# zhuzhuan1.net
KiCad netlist of a schematic drawn in Altium Designer
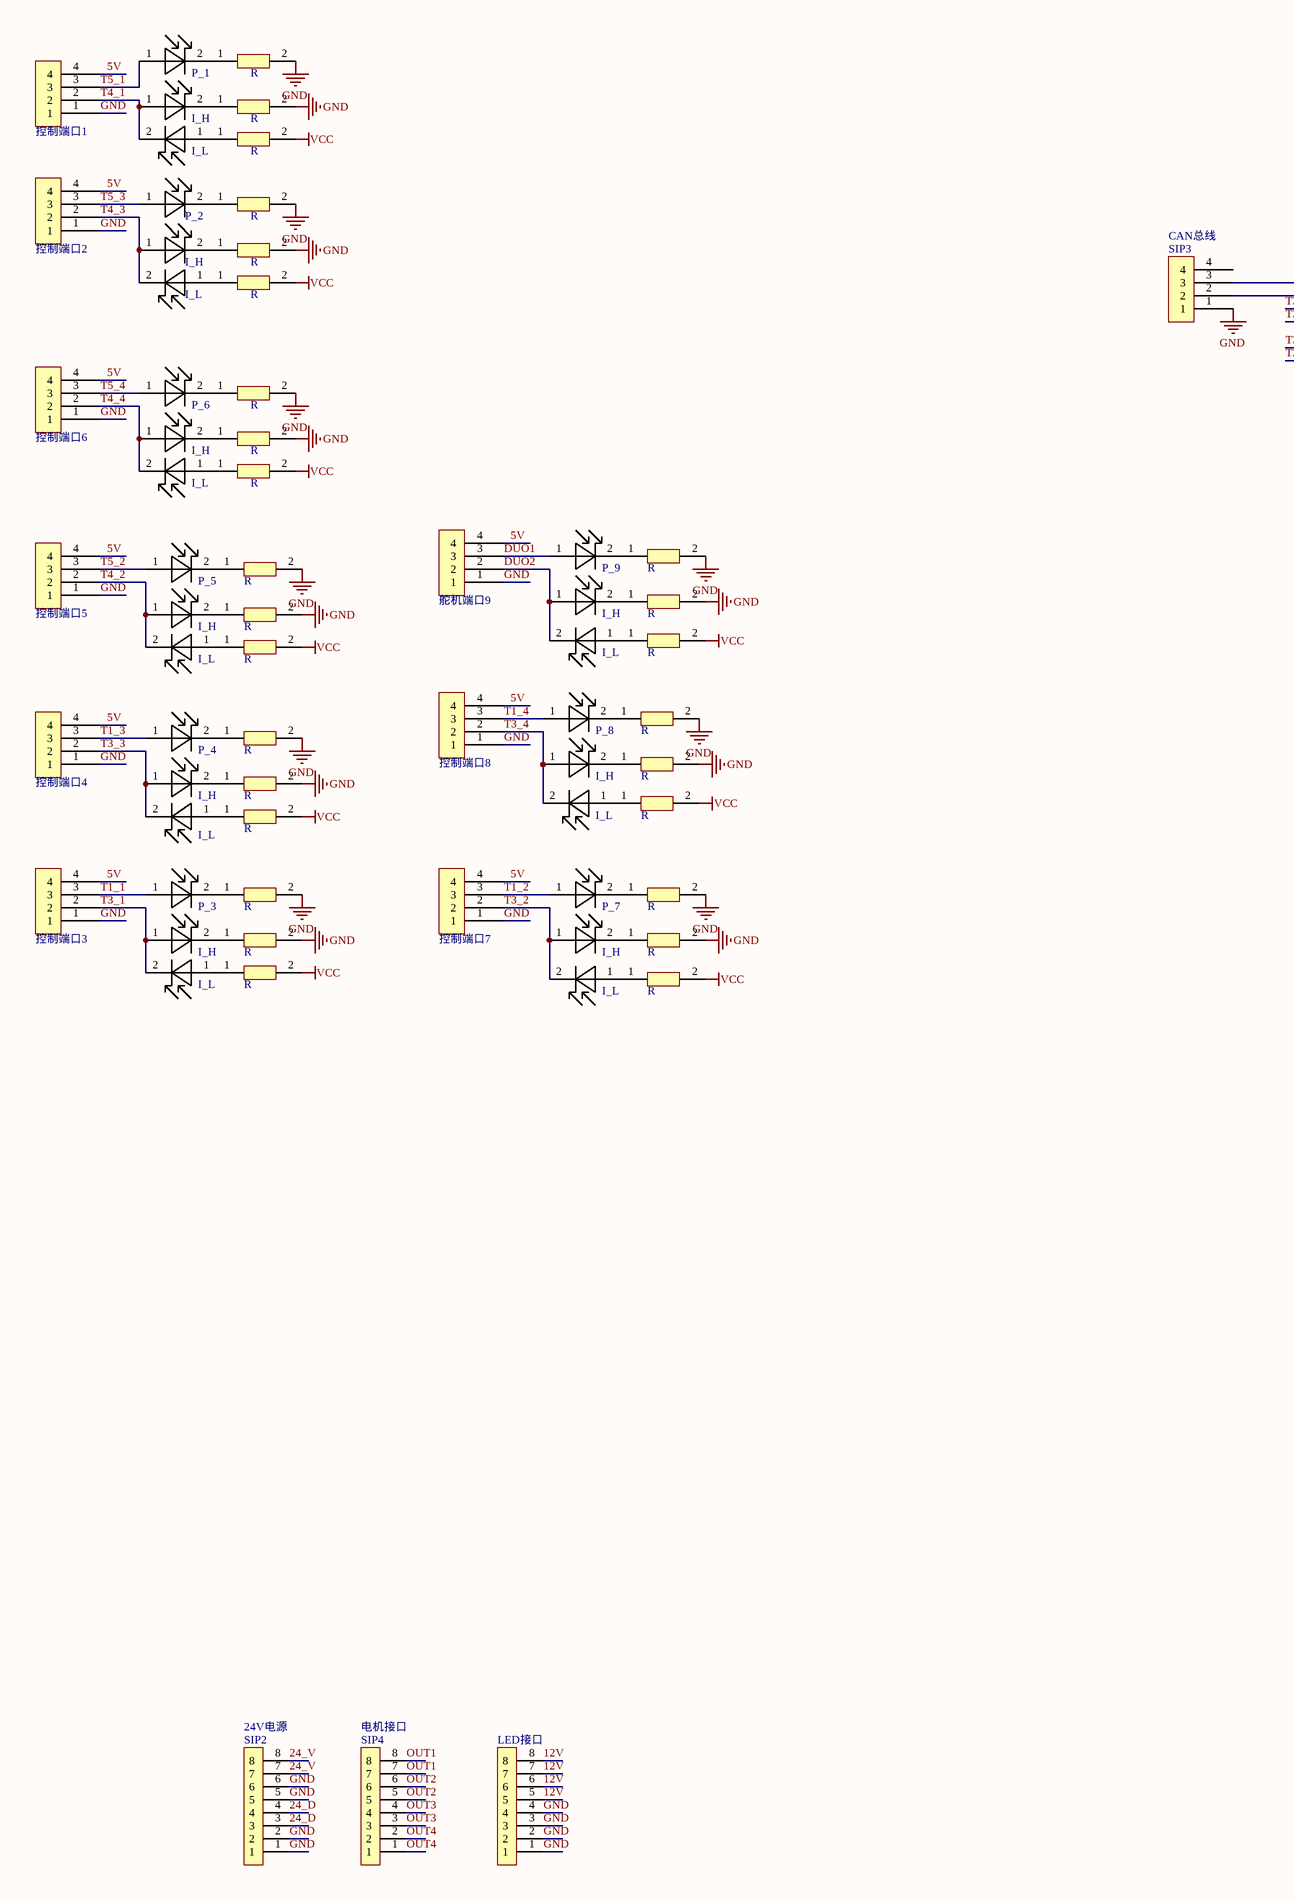
[diagram p0: zhuzhuan1.SchDoc, left]
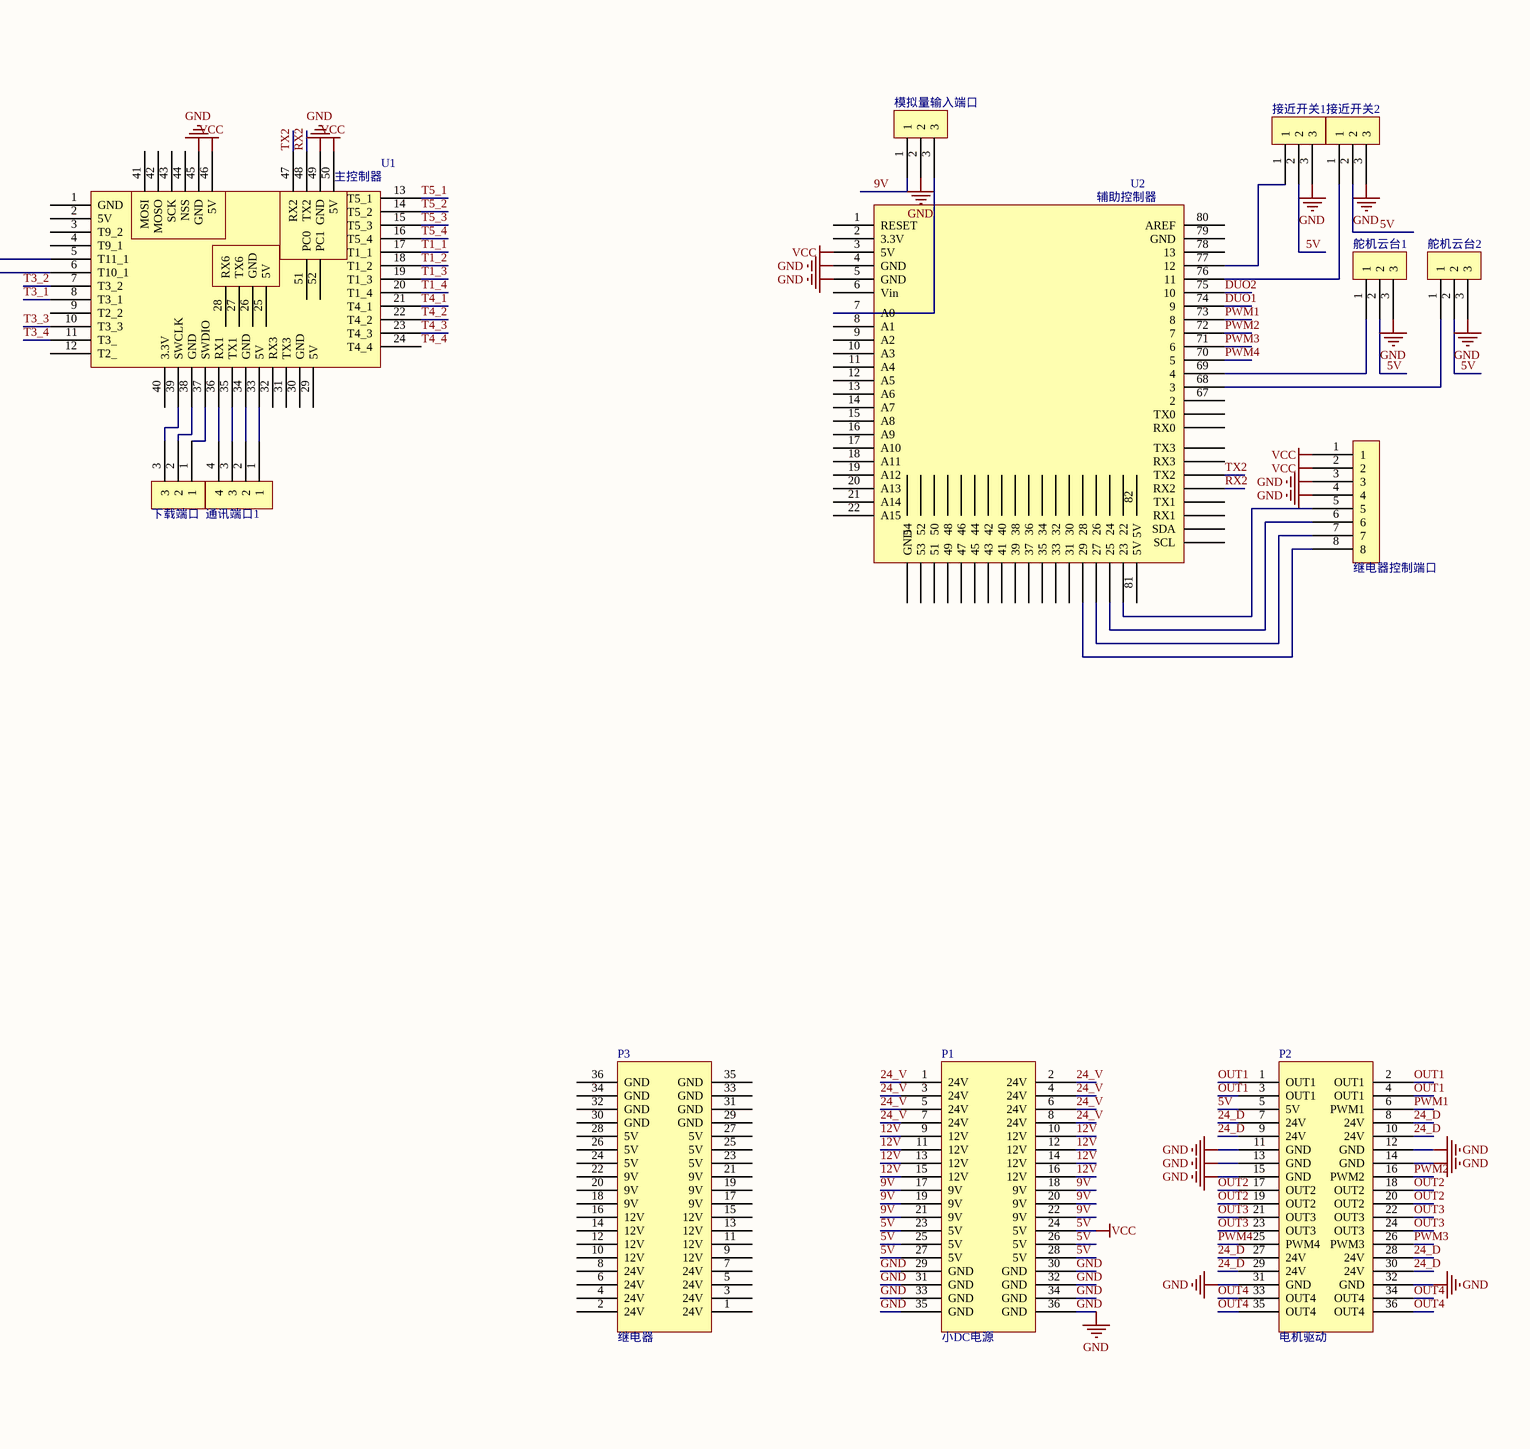
[diagram p1: zhuzhuan1.SchDoc, right]

(export (version "E")
  (design (tool "Eeschema 10.0.6"))
  (components
    (comp (ref "L1") (value "P_1") (footprint "LED-T") (libsource (lib "qudong") (part "LED")))
    (comp (ref "L2") (value "I_H") (footprint "LED-T") (libsource (lib "qudong") (part "LED")))
    (comp (ref "L3") (value "I_L") (footprint "LED-T") (libsource (lib "qudong") (part "LED")))
    (comp (ref "L4") (value "P_2") (footprint "LED-T") (libsource (lib "qudong") (part "LED")))
    (comp (ref "L5") (value "I_H") (footprint "LED-T") (libsource (lib "qudong") (part "LED")))
    (comp (ref "L6") (value "I_L") (footprint "LED-T") (libsource (lib "qudong") (part "LED")))
    (comp (ref "L7") (value "P_3") (footprint "LED-T") (libsource (lib "qudong") (part "LED")))
    (comp (ref "L8") (value "I_H") (footprint "LED-T") (libsource (lib "qudong") (part "LED")))
    (comp (ref "L9") (value "I_L") (footprint "LED-T") (libsource (lib "qudong") (part "LED")))
    (comp (ref "L10") (value "P_4") (footprint "LED-T") (libsource (lib "qudong") (part "LED")))
    (comp (ref "L11") (value "I_H") (footprint "LED-T") (libsource (lib "qudong") (part "LED")))
    (comp (ref "L12") (value "I_L") (footprint "LED-T") (libsource (lib "qudong") (part "LED")))
    (comp (ref "L13") (value "P_5") (footprint "LED-T") (libsource (lib "qudong") (part "LED")))
    (comp (ref "L14") (value "I_H") (footprint "LED-T") (libsource (lib "qudong") (part "LED")))
    (comp (ref "L15") (value "I_L") (footprint "LED-T") (libsource (lib "qudong") (part "LED")))
    (comp (ref "L16") (value "P_6") (footprint "LED-T") (libsource (lib "qudong") (part "LED")))
    (comp (ref "L17") (value "I_H") (footprint "LED-T") (libsource (lib "qudong") (part "LED")))
    (comp (ref "L18") (value "I_L") (footprint "LED-T") (libsource (lib "qudong") (part "LED")))
    (comp (ref "L19") (value "P_7") (footprint "LED-T") (libsource (lib "qudong") (part "LED")))
    (comp (ref "L20") (value "I_H") (footprint "LED-T") (libsource (lib "qudong") (part "LED")))
    (comp (ref "L21") (value "I_L") (footprint "LED-T") (libsource (lib "qudong") (part "LED")))
    (comp (ref "L22") (value "P_8") (footprint "LED-T") (libsource (lib "qudong") (part "LED")))
    (comp (ref "L23") (value "I_H") (footprint "LED-T") (libsource (lib "qudong") (part "LED")))
    (comp (ref "L24") (value "I_L") (footprint "LED-T") (libsource (lib "qudong") (part "LED")))
    (comp (ref "L25") (value "P_9") (footprint "LED-T") (libsource (lib "qudong") (part "LED")))
    (comp (ref "L26") (value "I_H") (footprint "LED-T") (libsource (lib "qudong") (part "LED")))
    (comp (ref "L27") (value "I_L") (footprint "LED-T") (libsource (lib "qudong") (part "LED")))
    (comp (ref "P1") (value "小DC电源") (footprint "DIP36-3.96MM") (libsource (lib "") (part "POWER_18*2_1")))
    (comp (ref "P2") (value "电机驱动") (footprint "DIP36-3.96MM") (libsource (lib "qudong") (part "Header")))
    (comp (ref "P3") (value "继电器") (footprint "DIP36-3.96MM") (libsource (lib "qudong") (part "POWER_18*2")))
    (comp (ref "R1") (value "R") (footprint "RES-T") (libsource (lib "qudong") (part "RES-T")))
    (comp (ref "R2") (value "R") (footprint "RES-T") (libsource (lib "qudong") (part "RES-T")))
    (comp (ref "R3") (value "R") (footprint "RES-T") (libsource (lib "qudong") (part "RES-T")))
    (comp (ref "R4") (value "R") (footprint "RES-T") (libsource (lib "qudong") (part "RES-T")))
    (comp (ref "R5") (value "R") (footprint "RES-T") (libsource (lib "qudong") (part "RES-T")))
    (comp (ref "R6") (value "R") (footprint "RES-T") (libsource (lib "qudong") (part "RES-T")))
    (comp (ref "R7") (value "R") (footprint "RES-T") (libsource (lib "qudong") (part "RES-T")))
    (comp (ref "R8") (value "R") (footprint "RES-T") (libsource (lib "qudong") (part "RES-T")))
    (comp (ref "R9") (value "R") (footprint "RES-T") (libsource (lib "qudong") (part "RES-T")))
    (comp (ref "R10") (value "R") (footprint "RES-T") (libsource (lib "qudong") (part "RES-T")))
    (comp (ref "R11") (value "R") (footprint "RES-T") (libsource (lib "qudong") (part "RES-T")))
    (comp (ref "R12") (value "R") (footprint "RES-T") (libsource (lib "qudong") (part "RES-T")))
    (comp (ref "R13") (value "R") (footprint "RES-T") (libsource (lib "qudong") (part "RES-T")))
    (comp (ref "R14") (value "R") (footprint "RES-T") (libsource (lib "qudong") (part "RES-T")))
    (comp (ref "R15") (value "R") (footprint "RES-T") (libsource (lib "qudong") (part "RES-T")))
    (comp (ref "R16") (value "R") (footprint "RES-T") (libsource (lib "qudong") (part "RES-T")))
    (comp (ref "R17") (value "R") (footprint "RES-T") (libsource (lib "qudong") (part "RES-T")))
    (comp (ref "R18") (value "R") (footprint "RES-T") (libsource (lib "qudong") (part "RES-T")))
    (comp (ref "R19") (value "R") (footprint "RES-T") (libsource (lib "qudong") (part "RES-T")))
    (comp (ref "R20") (value "R") (footprint "RES-T") (libsource (lib "qudong") (part "RES-T")))
    (comp (ref "R21") (value "R") (footprint "RES-T") (libsource (lib "qudong") (part "RES-T")))
    (comp (ref "R22") (value "R") (footprint "RES-T") (libsource (lib "qudong") (part "RES-T")))
    (comp (ref "R23") (value "R") (footprint "RES-T") (libsource (lib "qudong") (part "RES-T")))
    (comp (ref "R24") (value "R") (footprint "RES-T") (libsource (lib "qudong") (part "RES-T")))
    (comp (ref "R25") (value "R") (footprint "RES-T") (libsource (lib "qudong") (part "RES-T")))
    (comp (ref "R26") (value "R") (footprint "RES-T") (libsource (lib "qudong") (part "RES-T")))
    (comp (ref "R27") (value "R") (footprint "RES-T") (libsource (lib "qudong") (part "RES-T")))
    (comp (ref "SIP2") (value "24V电源") (footprint "SIP8*3MM") (libsource (lib "qudong") (part "SIP8*3MM")))
    (comp (ref "SIP3") (value "CAN总线") (footprint "SIP4") (libsource (lib "qudong") (part "SIP4")))
    (comp (ref "SIP4") (value "电机接口") (footprint "SIP8*3MM") (libsource (lib "qudong") (part "SIP8*3MM")))
    (comp (ref "SIP5") (value "下载端口") (footprint "SIP3") (libsource (lib "") (part "SIP3_1")))
    (comp (ref "SIP7") (value "控制端口1") (footprint "SIP4") (libsource (lib "qudong") (part "SIP4")))
    (comp (ref "SIP8") (value "控制端口2") (footprint "SIP4") (libsource (lib "qudong") (part "SIP4")))
    (comp (ref "SIP9") (value "控制端口3") (footprint "SIP4") (libsource (lib "qudong") (part "SIP4")))
    (comp (ref "SIP10") (value "控制端口4") (footprint "SIP4") (libsource (lib "qudong") (part "SIP4")))
    (comp (ref "SIP11") (value "控制端口5") (footprint "SIP4") (libsource (lib "qudong") (part "SIP4")))
    (comp (ref "SIP12") (value "控制端口6") (footprint "SIP4") (libsource (lib "qudong") (part "SIP4")))
    (comp (ref "SIP13") (value "控制端口7") (footprint "SIP4") (libsource (lib "qudong") (part "SIP4")))
    (comp (ref "SIP14") (value "控制端口8") (footprint "SIP4") (libsource (lib "qudong") (part "SIP4")))
    (comp (ref "SIP15") (value "舵机云台1") (footprint "SIP3-3MM") (libsource (lib "qudong") (part "SIP3")))
    (comp (ref "SIP16") (value "舵机云台2") (footprint "SIP3-3MM") (libsource (lib "qudong") (part "SIP3")))
    (comp (ref "SIP17") (value "模拟量输入端口") (footprint "SIP3-3MM") (libsource (lib "qudong") (part "SIP3")))
    (comp (ref "SIP18") (value "舵机端口9") (footprint "SIP4") (libsource (lib "qudong") (part "SIP4")))
    (comp (ref "SIP19") (value "LED接口") (footprint "SIP8*3MM") (libsource (lib "qudong") (part "SIP8*3MM")))
    (comp (ref "SIP20") (value "接近开关1") (footprint "SIP3-3MM") (libsource (lib "qudong") (part "SIP3")))
    (comp (ref "SIP21") (value "接近开关2") (footprint "SIP3-3MM") (libsource (lib "qudong") (part "SIP3")))
    (comp (ref "SIP22") (value "继电器控制端口") (footprint "SIP8") (libsource (lib "qudong") (part "SIP8")))
    (comp (ref "U1")
      (value "主控制器")
      (footprint "-----STM32F407-----")
      (libsource (lib "qudong") (part "------STM32F407------"))
    )
    (comp (ref "U2")
      (value "辅助控制器")
      (footprint "ARDUINO 2560")
      (libsource (lib "qudong") (part "ARDUINO 2560"))
    )
    (comp (ref "通讯端口1") (value "SIP4") (footprint "SIP4") (libsource (lib "") (part "SIP4_1")))
  )
  (nets
    (net (code "1") (name "/9V") (class "Default")
      (node (ref "P1") (pin "17") (pinfunction "9V_17") (pintype "passive"))
      (node (ref "P1") (pin "18") (pinfunction "9V_18") (pintype "passive"))
      (node (ref "P1") (pin "19") (pinfunction "9V_19") (pintype "passive"))
      (node (ref "P1") (pin "20") (pinfunction "9V_20") (pintype "passive"))
      (node (ref "P1") (pin "21") (pinfunction "9V_21") (pintype "passive"))
      (node (ref "P1") (pin "22") (pinfunction "9V_22") (pintype "passive"))
      (node (ref "SIP17") (pin "1") (pinfunction "1_1") (pintype "passive"))
    )
    (net (code "2") (name "/12V") (class "Default")
      (node (ref "P1") (pin "10") (pinfunction "12V_10") (pintype "passive"))
      (node (ref "P1") (pin "11") (pinfunction "12V_11") (pintype "passive"))
      (node (ref "P1") (pin "12") (pinfunction "12V_12") (pintype "passive"))
      (node (ref "P1") (pin "13") (pinfunction "12V_13") (pintype "passive"))
      (node (ref "P1") (pin "14") (pinfunction "12V_14") (pintype "passive"))
      (node (ref "P1") (pin "15") (pinfunction "12V_15") (pintype "passive"))
      (node (ref "P1") (pin "16") (pinfunction "12V_16") (pintype "passive"))
      (node (ref "P1") (pin "9") (pinfunction "12V_9") (pintype "passive"))
      (node (ref "SIP19") (pin "5") (pinfunction "5_5") (pintype "passive"))
      (node (ref "SIP19") (pin "6") (pinfunction "6_6") (pintype "passive"))
      (node (ref "SIP19") (pin "7") (pinfunction "7_7") (pintype "passive"))
      (node (ref "SIP19") (pin "8") (pinfunction "8_8") (pintype "passive"))
    )
    (net (code "3") (name "/24_D") (class "Default")
      (node (ref "P2") (pin "10") (pinfunction "24V_10") (pintype "passive"))
      (node (ref "P2") (pin "27") (pinfunction "24V_27") (pintype "passive"))
      (node (ref "P2") (pin "28") (pinfunction "24V_28") (pintype "passive"))
      (node (ref "P2") (pin "29") (pinfunction "24V_29") (pintype "passive"))
      (node (ref "P2") (pin "30") (pinfunction "24V_30") (pintype "passive"))
      (node (ref "P2") (pin "7") (pinfunction "24V_7") (pintype "passive"))
      (node (ref "P2") (pin "8") (pinfunction "24V_8") (pintype "passive"))
      (node (ref "P2") (pin "9") (pinfunction "24V_9") (pintype "passive"))
      (node (ref "SIP2") (pin "3") (pinfunction "3_3") (pintype "passive"))
      (node (ref "SIP2") (pin "4") (pinfunction "4_4") (pintype "passive"))
    )
    (net (code "4") (name "/24_V") (class "Default")
      (node (ref "P1") (pin "1") (pinfunction "24V_1") (pintype "passive"))
      (node (ref "P1") (pin "2") (pinfunction "24V_2") (pintype "passive"))
      (node (ref "P1") (pin "3") (pinfunction "24V_3") (pintype "passive"))
      (node (ref "P1") (pin "4") (pinfunction "24V_4") (pintype "passive"))
      (node (ref "P1") (pin "5") (pinfunction "24V_5") (pintype "passive"))
      (node (ref "P1") (pin "6") (pinfunction "24V_6") (pintype "passive"))
      (node (ref "P1") (pin "7") (pinfunction "24V_7") (pintype "passive"))
      (node (ref "P1") (pin "8") (pinfunction "24V_8") (pintype "passive"))
      (node (ref "SIP2") (pin "7") (pinfunction "7_7") (pintype "passive"))
      (node (ref "SIP2") (pin "8") (pinfunction "8_8") (pintype "passive"))
    )
    (net (code "5") (name "/DUO1") (class "Default")
      (node (ref "L25") (pin "1") (pinfunction "1_1") (pintype "passive"))
      (node (ref "SIP18") (pin "3") (pinfunction "3_3") (pintype "passive"))
      (node (ref "U2") (pin "74") (pinfunction "9_74") (pintype "passive"))
    )
    (net (code "6") (name "/DUO2") (class "Default")
      (node (ref "L26") (pin "1") (pinfunction "1_1") (pintype "passive"))
      (node (ref "L27") (pin "2") (pinfunction "2_2") (pintype "passive"))
      (node (ref "SIP18") (pin "2") (pinfunction "2_2") (pintype "passive"))
      (node (ref "U2") (pin "75") (pinfunction "10_75") (pintype "passive"))
    )
    (net (code "7") (name "/OUT1") (class "Default")
      (node (ref "P2") (pin "1") (pinfunction "OUT1_1") (pintype "passive"))
      (node (ref "P2") (pin "2") (pinfunction "OUT1_2") (pintype "passive"))
      (node (ref "P2") (pin "3") (pinfunction "OUT1_3") (pintype "passive"))
      (node (ref "P2") (pin "4") (pinfunction "OUT1_4") (pintype "passive"))
      (node (ref "SIP4") (pin "7") (pinfunction "7_7") (pintype "passive"))
      (node (ref "SIP4") (pin "8") (pinfunction "8_8") (pintype "passive"))
    )
    (net (code "8") (name "/OUT2") (class "Default")
      (node (ref "P2") (pin "17") (pinfunction "OUT2_17") (pintype "passive"))
      (node (ref "P2") (pin "18") (pinfunction "OUT2_18") (pintype "passive"))
      (node (ref "P2") (pin "19") (pinfunction "OUT2_19") (pintype "passive"))
      (node (ref "P2") (pin "20") (pinfunction "OUT2_20") (pintype "passive"))
      (node (ref "SIP4") (pin "5") (pinfunction "5_5") (pintype "passive"))
      (node (ref "SIP4") (pin "6") (pinfunction "6_6") (pintype "passive"))
    )
    (net (code "9") (name "/OUT3") (class "Default")
      (node (ref "P2") (pin "21") (pinfunction "OUT3_21") (pintype "passive"))
      (node (ref "P2") (pin "22") (pinfunction "OUT3_22") (pintype "passive"))
      (node (ref "P2") (pin "23") (pinfunction "OUT3_23") (pintype "passive"))
      (node (ref "P2") (pin "24") (pinfunction "OUT3_24") (pintype "passive"))
      (node (ref "SIP4") (pin "3") (pinfunction "3_3") (pintype "passive"))
      (node (ref "SIP4") (pin "4") (pinfunction "4_4") (pintype "passive"))
    )
    (net (code "10") (name "/OUT4") (class "Default")
      (node (ref "P2") (pin "33") (pinfunction "OUT4_33") (pintype "passive"))
      (node (ref "P2") (pin "34") (pinfunction "OUT4_34") (pintype "passive"))
      (node (ref "P2") (pin "35") (pinfunction "OUT4_35") (pintype "passive"))
      (node (ref "P2") (pin "36") (pinfunction "OUT4_36") (pintype "passive"))
      (node (ref "SIP4") (pin "1") (pinfunction "1_1") (pintype "passive"))
      (node (ref "SIP4") (pin "2") (pinfunction "2_2") (pintype "passive"))
    )
    (net (code "11") (name "/PWM1") (class "Default")
      (node (ref "P2") (pin "6") (pinfunction "PWM1_6") (pintype "passive"))
      (node (ref "U2") (pin "73") (pinfunction "8_73") (pintype "passive"))
    )
    (net (code "12") (name "/PWM2") (class "Default")
      (node (ref "P2") (pin "16") (pinfunction "PWM2_16") (pintype "passive"))
      (node (ref "U2") (pin "72") (pinfunction "7_72") (pintype "passive"))
    )
    (net (code "13") (name "/PWM3") (class "Default")
      (node (ref "P2") (pin "26") (pinfunction "PWM3_26") (pintype "passive"))
      (node (ref "U2") (pin "71") (pinfunction "6_71") (pintype "passive"))
    )
    (net (code "14") (name "/PWM4") (class "Default")
      (node (ref "P2") (pin "25") (pinfunction "PWM4_25") (pintype "passive"))
      (node (ref "U2") (pin "70") (pinfunction "5_70") (pintype "passive"))
    )
    (net (code "15") (name "/RX2") (class "Default")
      (node (ref "U1") (pin "48") (pinfunction "TX2_48") (pintype "passive"))
      (node (ref "U2") (pin "61") (pinfunction "RX2_61") (pintype "passive"))
    )
    (net (code "16") (name "/T1_1") (class "Default")
      (node (ref "L7") (pin "1") (pinfunction "1_1") (pintype "passive"))
      (node (ref "SIP9") (pin "3") (pinfunction "3_3") (pintype "passive"))
      (node (ref "U1") (pin "17") (pinfunction "T1_1_17") (pintype "passive"))
    )
    (net (code "17") (name "/T1_2") (class "Default")
      (node (ref "L19") (pin "1") (pinfunction "1_1") (pintype "passive"))
      (node (ref "SIP13") (pin "3") (pinfunction "3_3") (pintype "passive"))
      (node (ref "U1") (pin "18") (pinfunction "T1_2_18") (pintype "passive"))
    )
    (net (code "18") (name "/T1_3") (class "Default")
      (node (ref "L10") (pin "1") (pinfunction "1_1") (pintype "passive"))
      (node (ref "SIP10") (pin "3") (pinfunction "3_3") (pintype "passive"))
      (node (ref "U1") (pin "19") (pinfunction "T1_3_19") (pintype "passive"))
    )
    (net (code "19") (name "/T1_4") (class "Default")
      (node (ref "L22") (pin "1") (pinfunction "1_1") (pintype "passive"))
      (node (ref "SIP14") (pin "3") (pinfunction "3_3") (pintype "passive"))
      (node (ref "U1") (pin "20") (pinfunction "T1_4_20") (pintype "passive"))
    )
    (net (code "20") (name "/T3_1") (class "Default")
      (node (ref "L8") (pin "1") (pinfunction "1_1") (pintype "passive"))
      (node (ref "L9") (pin "2") (pinfunction "2_2") (pintype "passive"))
      (node (ref "SIP9") (pin "2") (pinfunction "2_2") (pintype "passive"))
      (node (ref "U1") (pin "8") (pinfunction "T3_1_8") (pintype "passive"))
    )
    (net (code "21") (name "/T3_2") (class "Default")
      (node (ref "L20") (pin "1") (pinfunction "1_1") (pintype "passive"))
      (node (ref "L21") (pin "2") (pinfunction "2_2") (pintype "passive"))
      (node (ref "SIP13") (pin "2") (pinfunction "2_2") (pintype "passive"))
      (node (ref "U1") (pin "7") (pinfunction "T3_2_7") (pintype "passive"))
    )
    (net (code "22") (name "/T3_3") (class "Default")
      (node (ref "L11") (pin "1") (pinfunction "1_1") (pintype "passive"))
      (node (ref "L12") (pin "2") (pinfunction "2_2") (pintype "passive"))
      (node (ref "SIP10") (pin "2") (pinfunction "2_2") (pintype "passive"))
      (node (ref "U1") (pin "10") (pinfunction "T3_3_10") (pintype "passive"))
    )
    (net (code "23") (name "/T3_4") (class "Default")
      (node (ref "L23") (pin "1") (pinfunction "1_1") (pintype "passive"))
      (node (ref "L24") (pin "2") (pinfunction "2_2") (pintype "passive"))
      (node (ref "SIP14") (pin "2") (pinfunction "2_2") (pintype "passive"))
      (node (ref "U1") (pin "11") (pinfunction "T3__11") (pintype "passive"))
    )
    (net (code "24") (name "/T4_1") (class "Default")
      (node (ref "L2") (pin "1") (pinfunction "1_1") (pintype "passive"))
      (node (ref "L3") (pin "2") (pinfunction "2_2") (pintype "passive"))
      (node (ref "SIP7") (pin "2") (pinfunction "2_2") (pintype "passive"))
      (node (ref "U1") (pin "21") (pinfunction "T4_1_21") (pintype "passive"))
    )
    (net (code "25") (name "/T4_2") (class "Default")
      (node (ref "L14") (pin "1") (pinfunction "1_1") (pintype "passive"))
      (node (ref "L15") (pin "2") (pinfunction "2_2") (pintype "passive"))
      (node (ref "SIP11") (pin "2") (pinfunction "2_2") (pintype "passive"))
      (node (ref "U1") (pin "22") (pinfunction "T4_2_22") (pintype "passive"))
    )
    (net (code "26") (name "/T4_3") (class "Default")
      (node (ref "L5") (pin "1") (pinfunction "1_1") (pintype "passive"))
      (node (ref "L6") (pin "2") (pinfunction "2_2") (pintype "passive"))
      (node (ref "SIP8") (pin "2") (pinfunction "2_2") (pintype "passive"))
      (node (ref "U1") (pin "23") (pinfunction "T4_3_23") (pintype "passive"))
    )
    (net (code "27") (name "/T4_4") (class "Default")
      (node (ref "L17") (pin "1") (pinfunction "1_1") (pintype "passive"))
      (node (ref "L18") (pin "2") (pinfunction "2_2") (pintype "passive"))
      (node (ref "SIP12") (pin "2") (pinfunction "2_2") (pintype "passive"))
      (node (ref "U1") (pin "24") (pinfunction "T4_4_24") (pintype "passive"))
    )
    (net (code "28") (name "/T5_1") (class "Default")
      (node (ref "L1") (pin "1") (pinfunction "1_1") (pintype "passive"))
      (node (ref "SIP7") (pin "3") (pinfunction "3_3") (pintype "passive"))
      (node (ref "U1") (pin "13") (pinfunction "T5_1_13") (pintype "passive"))
    )
    (net (code "29") (name "/T5_2") (class "Default")
      (node (ref "L13") (pin "1") (pinfunction "1_1") (pintype "passive"))
      (node (ref "SIP11") (pin "3") (pinfunction "3_3") (pintype "passive"))
      (node (ref "U1") (pin "14") (pinfunction "T5_2_14") (pintype "passive"))
    )
    (net (code "30") (name "/T5_3") (class "Default")
      (node (ref "L4") (pin "1") (pinfunction "1_1") (pintype "passive"))
      (node (ref "SIP8") (pin "3") (pinfunction "3_3") (pintype "passive"))
      (node (ref "U1") (pin "15") (pinfunction "T5_3_15") (pintype "passive"))
    )
    (net (code "31") (name "/T5_4") (class "Default")
      (node (ref "L16") (pin "1") (pinfunction "1_1") (pintype "passive"))
      (node (ref "SIP12") (pin "3") (pinfunction "3_3") (pintype "passive"))
      (node (ref "U1") (pin "16") (pinfunction "T5_4_16") (pintype "passive"))
    )
    (net (code "32") (name "/TX2") (class "Default")
      (node (ref "U1") (pin "47") (pinfunction "RX2_47") (pintype "passive"))
      (node (ref "U2") (pin "62") (pinfunction "TX2_62") (pintype "passive"))
    )
    (net (code "33") (name "GND") (class "Default")
      (node (ref "P1") (pin "29") (pinfunction "GND_29") (pintype "passive"))
      (node (ref "P1") (pin "30") (pinfunction "GND_30") (pintype "passive"))
      (node (ref "P1") (pin "31") (pinfunction "GND_31") (pintype "passive"))
      (node (ref "P1") (pin "32") (pinfunction "GND_32") (pintype "passive"))
      (node (ref "P1") (pin "33") (pinfunction "GND_33") (pintype "passive"))
      (node (ref "P1") (pin "34") (pinfunction "GND_34") (pintype "passive"))
      (node (ref "P1") (pin "35") (pinfunction "GND_35") (pintype "passive"))
      (node (ref "P1") (pin "36") (pinfunction "GND_36") (pintype "passive"))
      (node (ref "P2") (pin "11") (pinfunction "GND_11") (pintype "passive"))
      (node (ref "P2") (pin "12") (pinfunction "GND_12") (pintype "passive"))
      (node (ref "P2") (pin "13") (pinfunction "GND_13") (pintype "passive"))
      (node (ref "P2") (pin "14") (pinfunction "GND_14") (pintype "passive"))
      (node (ref "P2") (pin "15") (pinfunction "GND_15") (pintype "passive"))
      (node (ref "P2") (pin "31") (pinfunction "GND_31") (pintype "passive"))
      (node (ref "P2") (pin "32") (pinfunction "GND_32") (pintype "passive"))
      (node (ref "R1") (pin "2") (pinfunction "2_2") (pintype "passive"))
      (node (ref "R10") (pin "2") (pinfunction "2_2") (pintype "passive"))
      (node (ref "R11") (pin "2") (pinfunction "2_2") (pintype "passive"))
      (node (ref "R13") (pin "2") (pinfunction "2_2") (pintype "passive"))
      (node (ref "R14") (pin "2") (pinfunction "2_2") (pintype "passive"))
      (node (ref "R16") (pin "2") (pinfunction "2_2") (pintype "passive"))
      (node (ref "R17") (pin "2") (pinfunction "2_2") (pintype "passive"))
      (node (ref "R19") (pin "2") (pinfunction "2_2") (pintype "passive"))
      (node (ref "R2") (pin "2") (pinfunction "2_2") (pintype "passive"))
      (node (ref "R20") (pin "2") (pinfunction "2_2") (pintype "passive"))
      (node (ref "R22") (pin "2") (pinfunction "2_2") (pintype "passive"))
      (node (ref "R23") (pin "2") (pinfunction "2_2") (pintype "passive"))
      (node (ref "R25") (pin "2") (pinfunction "2_2") (pintype "passive"))
      (node (ref "R26") (pin "2") (pinfunction "2_2") (pintype "passive"))
      (node (ref "R4") (pin "2") (pinfunction "2_2") (pintype "passive"))
      (node (ref "R5") (pin "2") (pinfunction "2_2") (pintype "passive"))
      (node (ref "R7") (pin "2") (pinfunction "2_2") (pintype "passive"))
      (node (ref "R8") (pin "2") (pinfunction "2_2") (pintype "passive"))
      (node (ref "SIP10") (pin "1") (pinfunction "1_1") (pintype "passive"))
      (node (ref "SIP11") (pin "1") (pinfunction "1_1") (pintype "passive"))
      (node (ref "SIP12") (pin "1") (pinfunction "1_1") (pintype "passive"))
      (node (ref "SIP13") (pin "1") (pinfunction "1_1") (pintype "passive"))
      (node (ref "SIP14") (pin "1") (pinfunction "1_1") (pintype "passive"))
      (node (ref "SIP15") (pin "3") (pinfunction "3_3") (pintype "passive"))
      (node (ref "SIP16") (pin "3") (pinfunction "3_3") (pintype "passive"))
      (node (ref "SIP17") (pin "2") (pinfunction "2_2") (pintype "passive"))
      (node (ref "SIP18") (pin "1") (pinfunction "1_1") (pintype "passive"))
      (node (ref "SIP19") (pin "1") (pinfunction "1_1") (pintype "passive"))
      (node (ref "SIP19") (pin "2") (pinfunction "2_2") (pintype "passive"))
      (node (ref "SIP19") (pin "3") (pinfunction "3_3") (pintype "passive"))
      (node (ref "SIP19") (pin "4") (pinfunction "4_4") (pintype "passive"))
      (node (ref "SIP2") (pin "1") (pinfunction "1_1") (pintype "passive"))
      (node (ref "SIP2") (pin "2") (pinfunction "2_2") (pintype "passive"))
      (node (ref "SIP2") (pin "5") (pinfunction "5_5") (pintype "passive"))
      (node (ref "SIP2") (pin "6") (pinfunction "6_6") (pintype "passive"))
      (node (ref "SIP20") (pin "3") (pinfunction "3_3") (pintype "passive"))
      (node (ref "SIP21") (pin "3") (pinfunction "3_3") (pintype "passive"))
      (node (ref "SIP22") (pin "3") (pinfunction "3_3") (pintype "passive"))
      (node (ref "SIP22") (pin "4") (pinfunction "4_4") (pintype "passive"))
      (node (ref "SIP3") (pin "1") (pinfunction "1_1") (pintype "passive"))
      (node (ref "SIP7") (pin "1") (pinfunction "1_1") (pintype "passive"))
      (node (ref "SIP8") (pin "1") (pinfunction "1_1") (pintype "passive"))
      (node (ref "SIP9") (pin "1") (pinfunction "1_1") (pintype "passive"))
      (node (ref "U1") (pin "45") (pinfunction "GND_45") (pintype "passive"))
      (node (ref "U1") (pin "49") (pinfunction "GND_49") (pintype "passive"))
      (node (ref "U2") (pin "4") (pinfunction "GND_4") (pintype "passive"))
      (node (ref "U2") (pin "5") (pinfunction "GND_5") (pintype "passive"))
    )
    (net (code "34") (name "Net-(L1-Pad2)") (class "Default")
      (node (ref "L1") (pin "2") (pinfunction "2_2") (pintype "passive"))
      (node (ref "R1") (pin "1") (pinfunction "1_1") (pintype "passive"))
    )
    (net (code "35") (name "Net-(L2-Pad2)") (class "Default")
      (node (ref "L2") (pin "2") (pinfunction "2_2") (pintype "passive"))
      (node (ref "R2") (pin "1") (pinfunction "1_1") (pintype "passive"))
    )
    (net (code "36") (name "Net-(L3-Pad1)") (class "Default")
      (node (ref "L3") (pin "1") (pinfunction "1_1") (pintype "passive"))
      (node (ref "R3") (pin "1") (pinfunction "1_1") (pintype "passive"))
    )
    (net (code "37") (name "Net-(L4-Pad2)") (class "Default")
      (node (ref "L4") (pin "2") (pinfunction "2_2") (pintype "passive"))
      (node (ref "R4") (pin "1") (pinfunction "1_1") (pintype "passive"))
    )
    (net (code "38") (name "Net-(L5-Pad2)") (class "Default")
      (node (ref "L5") (pin "2") (pinfunction "2_2") (pintype "passive"))
      (node (ref "R5") (pin "1") (pinfunction "1_1") (pintype "passive"))
    )
    (net (code "39") (name "Net-(L6-Pad1)") (class "Default")
      (node (ref "L6") (pin "1") (pinfunction "1_1") (pintype "passive"))
      (node (ref "R6") (pin "1") (pinfunction "1_1") (pintype "passive"))
    )
    (net (code "40") (name "Net-(L7-Pad2)") (class "Default")
      (node (ref "L7") (pin "2") (pinfunction "2_2") (pintype "passive"))
      (node (ref "R7") (pin "1") (pinfunction "1_1") (pintype "passive"))
    )
    (net (code "41") (name "Net-(L8-Pad2)") (class "Default")
      (node (ref "L8") (pin "2") (pinfunction "2_2") (pintype "passive"))
      (node (ref "R8") (pin "1") (pinfunction "1_1") (pintype "passive"))
    )
    (net (code "42") (name "Net-(L9-Pad1)") (class "Default")
      (node (ref "L9") (pin "1") (pinfunction "1_1") (pintype "passive"))
      (node (ref "R9") (pin "1") (pinfunction "1_1") (pintype "passive"))
    )
    (net (code "43") (name "Net-(L10-Pad2)") (class "Default")
      (node (ref "L10") (pin "2") (pinfunction "2_2") (pintype "passive"))
      (node (ref "R10") (pin "1") (pinfunction "1_1") (pintype "passive"))
    )
    (net (code "44") (name "Net-(L11-Pad2)") (class "Default")
      (node (ref "L11") (pin "2") (pinfunction "2_2") (pintype "passive"))
      (node (ref "R11") (pin "1") (pinfunction "1_1") (pintype "passive"))
    )
    (net (code "45") (name "Net-(L12-Pad1)") (class "Default")
      (node (ref "L12") (pin "1") (pinfunction "1_1") (pintype "passive"))
      (node (ref "R12") (pin "1") (pinfunction "1_1") (pintype "passive"))
    )
    (net (code "46") (name "Net-(L13-Pad2)") (class "Default")
      (node (ref "L13") (pin "2") (pinfunction "2_2") (pintype "passive"))
      (node (ref "R13") (pin "1") (pinfunction "1_1") (pintype "passive"))
    )
    (net (code "47") (name "Net-(L14-Pad2)") (class "Default")
      (node (ref "L14") (pin "2") (pinfunction "2_2") (pintype "passive"))
      (node (ref "R14") (pin "1") (pinfunction "1_1") (pintype "passive"))
    )
    (net (code "48") (name "Net-(L15-Pad1)") (class "Default")
      (node (ref "L15") (pin "1") (pinfunction "1_1") (pintype "passive"))
      (node (ref "R15") (pin "1") (pinfunction "1_1") (pintype "passive"))
    )
    (net (code "49") (name "Net-(L16-Pad2)") (class "Default")
      (node (ref "L16") (pin "2") (pinfunction "2_2") (pintype "passive"))
      (node (ref "R16") (pin "1") (pinfunction "1_1") (pintype "passive"))
    )
    (net (code "50") (name "Net-(L17-Pad2)") (class "Default")
      (node (ref "L17") (pin "2") (pinfunction "2_2") (pintype "passive"))
      (node (ref "R17") (pin "1") (pinfunction "1_1") (pintype "passive"))
    )
    (net (code "51") (name "Net-(L18-Pad1)") (class "Default")
      (node (ref "L18") (pin "1") (pinfunction "1_1") (pintype "passive"))
      (node (ref "R18") (pin "1") (pinfunction "1_1") (pintype "passive"))
    )
    (net (code "52") (name "Net-(L19-Pad2)") (class "Default")
      (node (ref "L19") (pin "2") (pinfunction "2_2") (pintype "passive"))
      (node (ref "R19") (pin "1") (pinfunction "1_1") (pintype "passive"))
    )
    (net (code "53") (name "Net-(L20-Pad2)") (class "Default")
      (node (ref "L20") (pin "2") (pinfunction "2_2") (pintype "passive"))
      (node (ref "R20") (pin "1") (pinfunction "1_1") (pintype "passive"))
    )
    (net (code "54") (name "Net-(L21-Pad1)") (class "Default")
      (node (ref "L21") (pin "1") (pinfunction "1_1") (pintype "passive"))
      (node (ref "R21") (pin "1") (pinfunction "1_1") (pintype "passive"))
    )
    (net (code "55") (name "Net-(L22-Pad2)") (class "Default")
      (node (ref "L22") (pin "2") (pinfunction "2_2") (pintype "passive"))
      (node (ref "R22") (pin "1") (pinfunction "1_1") (pintype "passive"))
    )
    (net (code "56") (name "Net-(L23-Pad2)") (class "Default")
      (node (ref "L23") (pin "2") (pinfunction "2_2") (pintype "passive"))
      (node (ref "R23") (pin "1") (pinfunction "1_1") (pintype "passive"))
    )
    (net (code "57") (name "Net-(L24-Pad1)") (class "Default")
      (node (ref "L24") (pin "1") (pinfunction "1_1") (pintype "passive"))
      (node (ref "R24") (pin "1") (pinfunction "1_1") (pintype "passive"))
    )
    (net (code "58") (name "Net-(L25-Pad2)") (class "Default")
      (node (ref "L25") (pin "2") (pinfunction "2_2") (pintype "passive"))
      (node (ref "R25") (pin "1") (pinfunction "1_1") (pintype "passive"))
    )
    (net (code "59") (name "Net-(L26-Pad2)") (class "Default")
      (node (ref "L26") (pin "2") (pinfunction "2_2") (pintype "passive"))
      (node (ref "R26") (pin "1") (pinfunction "1_1") (pintype "passive"))
    )
    (net (code "60") (name "Net-(L27-Pad1)") (class "Default")
      (node (ref "L27") (pin "1") (pinfunction "1_1") (pintype "passive"))
      (node (ref "R27") (pin "1") (pinfunction "1_1") (pintype "passive"))
    )
    (net (code "61") (name "Net-(SIP5-Pad2)") (class "Default")
      (node (ref "SIP5") (pin "2") (pinfunction "2_2") (pintype "passive"))
      (node (ref "U1") (pin "38") (pinfunction "GND_38") (pintype "passive"))
    )
    (net (code "62") (name "Net-(U1-5V-Pad33)") (class "Default")
      (node (ref "U1") (pin "33") (pinfunction "5V_33") (pintype "passive"))
      (node (ref "通讯端口1") (pin "1") (pinfunction "1_1") (pintype "passive"))
    )
    (net (code "63") (name "Net-(U1-GND-Pad34)") (class "Default")
      (node (ref "U1") (pin "34") (pinfunction "GND_34") (pintype "passive"))
      (node (ref "通讯端口1") (pin "2") (pinfunction "2_2") (pintype "passive"))
    )
    (net (code "64") (name "Net-(U1-RX1)") (class "Default")
      (node (ref "U1") (pin "36") (pinfunction "RX1_36") (pintype "passive"))
      (node (ref "通讯端口1") (pin "4") (pinfunction "4_4") (pintype "passive"))
    )
    (net (code "65") (name "Net-(U1-SWCLK)") (class "Default")
      (node (ref "SIP5") (pin "3") (pinfunction "3_3") (pintype "passive"))
      (node (ref "U1") (pin "39") (pinfunction "SWCLK_39") (pintype "passive"))
    )
    (net (code "66") (name "Net-(U1-SWDIO)") (class "Default")
      (node (ref "SIP5") (pin "1") (pinfunction "1_1") (pintype "passive"))
      (node (ref "U1") (pin "37") (pinfunction "SWDIO_37") (pintype "passive"))
    )
    (net (code "67") (name "Net-(U1-T10_1)") (class "Default")
      (node (ref "SIP3") (pin "2") (pinfunction "2_2") (pintype "passive"))
      (node (ref "U1") (pin "6") (pinfunction "T10_1_6") (pintype "passive"))
    )
    (net (code "68") (name "Net-(U1-T11_1)") (class "Default")
      (node (ref "SIP3") (pin "3") (pinfunction "3_3") (pintype "passive"))
      (node (ref "U1") (pin "5") (pinfunction "T11_1_5") (pintype "passive"))
    )
    (net (code "69") (name "Net-(U1-TX1)") (class "Default")
      (node (ref "U1") (pin "35") (pinfunction "TX1_35") (pintype "passive"))
      (node (ref "通讯端口1") (pin "3") (pinfunction "3_3") (pintype "passive"))
    )
    (net (code "70") (name "Net-(U2-3)") (class "Default")
      (node (ref "SIP16") (pin "1") (pinfunction "1_1") (pintype "passive"))
      (node (ref "U2") (pin "68") (pinfunction "3_68") (pintype "passive"))
    )
    (net (code "71") (name "Net-(U2-4)") (class "Default")
      (node (ref "SIP15") (pin "1") (pinfunction "1_1") (pintype "passive"))
      (node (ref "U2") (pin "69") (pinfunction "4_69") (pintype "passive"))
    )
    (net (code "72") (name "Net-(U2-11)") (class "Default")
      (node (ref "SIP21") (pin "1") (pinfunction "1_1") (pintype "passive"))
      (node (ref "U2") (pin "76") (pinfunction "11_76") (pintype "passive"))
    )
    (net (code "73") (name "Net-(U2-12)") (class "Default")
      (node (ref "SIP20") (pin "1") (pinfunction "1_1") (pintype "passive"))
      (node (ref "U2") (pin "77") (pinfunction "12_77") (pintype "passive"))
    )
    (net (code "74") (name "Net-(U2-23)") (class "Default")
      (node (ref "SIP22") (pin "5") (pinfunction "5_5") (pintype "passive"))
      (node (ref "U2") (pin "24") (pinfunction "23_24") (pintype "passive"))
    )
    (net (code "75") (name "Net-(U2-25)") (class "Default")
      (node (ref "SIP22") (pin "6") (pinfunction "6_6") (pintype "passive"))
      (node (ref "U2") (pin "26") (pinfunction "25_26") (pintype "passive"))
    )
    (net (code "76") (name "Net-(U2-27)") (class "Default")
      (node (ref "SIP22") (pin "7") (pinfunction "7_7") (pintype "passive"))
      (node (ref "U2") (pin "28") (pinfunction "27_28") (pintype "passive"))
    )
    (net (code "77") (name "Net-(U2-29)") (class "Default")
      (node (ref "SIP22") (pin "8") (pinfunction "8_8") (pintype "passive"))
      (node (ref "U2") (pin "30") (pinfunction "29_30") (pintype "passive"))
    )
    (net (code "78") (name "Net-(U2-A0)") (class "Default")
      (node (ref "SIP17") (pin "3") (pinfunction "3_3") (pintype "passive"))
      (node (ref "U2") (pin "7") (pinfunction "A0_7") (pintype "passive"))
    )
    (net (code "79") (name "VCC") (class "Default")
      (node (ref "P1") (pin "23") (pinfunction "5V_23") (pintype "passive"))
      (node (ref "P1") (pin "24") (pinfunction "5V_24") (pintype "passive"))
      (node (ref "P1") (pin "25") (pinfunction "5V_25") (pintype "passive"))
      (node (ref "P1") (pin "26") (pinfunction "5V_26") (pintype "passive"))
      (node (ref "P1") (pin "27") (pinfunction "5V_27") (pintype "passive"))
      (node (ref "P1") (pin "28") (pinfunction "5V_28") (pintype "passive"))
      (node (ref "P2") (pin "5") (pinfunction "5V_5") (pintype "passive"))
      (node (ref "R12") (pin "2") (pinfunction "2_2") (pintype "passive"))
      (node (ref "R15") (pin "2") (pinfunction "2_2") (pintype "passive"))
      (node (ref "R18") (pin "2") (pinfunction "2_2") (pintype "passive"))
      (node (ref "R21") (pin "2") (pinfunction "2_2") (pintype "passive"))
      (node (ref "R24") (pin "2") (pinfunction "2_2") (pintype "passive"))
      (node (ref "R27") (pin "2") (pinfunction "2_2") (pintype "passive"))
      (node (ref "R3") (pin "2") (pinfunction "2_2") (pintype "passive"))
      (node (ref "R6") (pin "2") (pinfunction "2_2") (pintype "passive"))
      (node (ref "R9") (pin "2") (pinfunction "2_2") (pintype "passive"))
      (node (ref "SIP10") (pin "4") (pinfunction "4_4") (pintype "passive"))
      (node (ref "SIP11") (pin "4") (pinfunction "4_4") (pintype "passive"))
      (node (ref "SIP12") (pin "4") (pinfunction "4_4") (pintype "passive"))
      (node (ref "SIP13") (pin "4") (pinfunction "4_4") (pintype "passive"))
      (node (ref "SIP14") (pin "4") (pinfunction "4_4") (pintype "passive"))
      (node (ref "SIP15") (pin "2") (pinfunction "2_2") (pintype "passive"))
      (node (ref "SIP16") (pin "2") (pinfunction "2_2") (pintype "passive"))
      (node (ref "SIP18") (pin "4") (pinfunction "4_4") (pintype "passive"))
      (node (ref "SIP20") (pin "2") (pinfunction "2_2") (pintype "passive"))
      (node (ref "SIP21") (pin "2") (pinfunction "2_2") (pintype "passive"))
      (node (ref "SIP22") (pin "1") (pinfunction "1_1") (pintype "passive"))
      (node (ref "SIP22") (pin "2") (pinfunction "2_2") (pintype "passive"))
      (node (ref "SIP7") (pin "4") (pinfunction "4_4") (pintype "passive"))
      (node (ref "SIP8") (pin "4") (pinfunction "4_4") (pintype "passive"))
      (node (ref "SIP9") (pin "4") (pinfunction "4_4") (pintype "passive"))
      (node (ref "U1") (pin "46") (pinfunction "5V_46") (pintype "passive"))
      (node (ref "U1") (pin "50") (pinfunction "5V_50") (pintype "passive"))
      (node (ref "U2") (pin "3") (pinfunction "5V_3") (pintype "passive"))
    )
    (net (code "80") (name "unconnected-(P3-5V-Pad23)") (class "Default")
      (node (ref "P3") (pin "23") (pinfunction "5V_23") (pintype "passive"))
    )
    (net (code "81") (name "unconnected-(P3-5V-Pad24)") (class "Default")
      (node (ref "P3") (pin "24") (pinfunction "5V_24") (pintype "passive"))
    )
    (net (code "82") (name "unconnected-(P3-5V-Pad25)") (class "Default")
      (node (ref "P3") (pin "25") (pinfunction "5V_25") (pintype "passive"))
    )
    (net (code "83") (name "unconnected-(P3-5V-Pad26)") (class "Default")
      (node (ref "P3") (pin "26") (pinfunction "5V_26") (pintype "passive"))
    )
    (net (code "84") (name "unconnected-(P3-5V-Pad27)") (class "Default")
      (node (ref "P3") (pin "27") (pinfunction "5V_27") (pintype "passive"))
    )
    (net (code "85") (name "unconnected-(P3-5V-Pad28)") (class "Default")
      (node (ref "P3") (pin "28") (pinfunction "5V_28") (pintype "passive"))
    )
    (net (code "86") (name "unconnected-(P3-9V-Pad17)") (class "Default")
      (node (ref "P3") (pin "17") (pinfunction "9V_17") (pintype "passive"))
    )
    (net (code "87") (name "unconnected-(P3-9V-Pad18)") (class "Default")
      (node (ref "P3") (pin "18") (pinfunction "9V_18") (pintype "passive"))
    )
    (net (code "88") (name "unconnected-(P3-9V-Pad19)") (class "Default")
      (node (ref "P3") (pin "19") (pinfunction "9V_19") (pintype "passive"))
    )
    (net (code "89") (name "unconnected-(P3-9V-Pad20)") (class "Default")
      (node (ref "P3") (pin "20") (pinfunction "9V_20") (pintype "passive"))
    )
    (net (code "90") (name "unconnected-(P3-9V-Pad21)") (class "Default")
      (node (ref "P3") (pin "21") (pinfunction "9V_21") (pintype "passive"))
    )
    (net (code "91") (name "unconnected-(P3-9V-Pad22)") (class "Default")
      (node (ref "P3") (pin "22") (pinfunction "9V_22") (pintype "passive"))
    )
    (net (code "92") (name "unconnected-(P3-12V-Pad9)") (class "Default")
      (node (ref "P3") (pin "9") (pinfunction "12V_9") (pintype "passive"))
    )
    (net (code "93") (name "unconnected-(P3-12V-Pad10)") (class "Default")
      (node (ref "P3") (pin "10") (pinfunction "12V_10") (pintype "passive"))
    )
    (net (code "94") (name "unconnected-(P3-12V-Pad11)") (class "Default")
      (node (ref "P3") (pin "11") (pinfunction "12V_11") (pintype "passive"))
    )
    (net (code "95") (name "unconnected-(P3-12V-Pad12)") (class "Default")
      (node (ref "P3") (pin "12") (pinfunction "12V_12") (pintype "passive"))
    )
    (net (code "96") (name "unconnected-(P3-12V-Pad13)") (class "Default")
      (node (ref "P3") (pin "13") (pinfunction "12V_13") (pintype "passive"))
    )
    (net (code "97") (name "unconnected-(P3-12V-Pad14)") (class "Default")
      (node (ref "P3") (pin "14") (pinfunction "12V_14") (pintype "passive"))
    )
    (net (code "98") (name "unconnected-(P3-12V-Pad15)") (class "Default")
      (node (ref "P3") (pin "15") (pinfunction "12V_15") (pintype "passive"))
    )
    (net (code "99") (name "unconnected-(P3-12V-Pad16)") (class "Default")
      (node (ref "P3") (pin "16") (pinfunction "12V_16") (pintype "passive"))
    )
    (net (code "100") (name "unconnected-(P3-24V-Pad1)") (class "Default")
      (node (ref "P3") (pin "1") (pinfunction "24V_1") (pintype "passive"))
    )
    (net (code "101") (name "unconnected-(P3-24V-Pad2)") (class "Default")
      (node (ref "P3") (pin "2") (pinfunction "24V_2") (pintype "passive"))
    )
    (net (code "102") (name "unconnected-(P3-24V-Pad3)") (class "Default")
      (node (ref "P3") (pin "3") (pinfunction "24V_3") (pintype "passive"))
    )
    (net (code "103") (name "unconnected-(P3-24V-Pad4)") (class "Default")
      (node (ref "P3") (pin "4") (pinfunction "24V_4") (pintype "passive"))
    )
    (net (code "104") (name "unconnected-(P3-24V-Pad5)") (class "Default")
      (node (ref "P3") (pin "5") (pinfunction "24V_5") (pintype "passive"))
    )
    (net (code "105") (name "unconnected-(P3-24V-Pad6)") (class "Default")
      (node (ref "P3") (pin "6") (pinfunction "24V_6") (pintype "passive"))
    )
    (net (code "106") (name "unconnected-(P3-24V-Pad7)") (class "Default")
      (node (ref "P3") (pin "7") (pinfunction "24V_7") (pintype "passive"))
    )
    (net (code "107") (name "unconnected-(P3-24V-Pad8)") (class "Default")
      (node (ref "P3") (pin "8") (pinfunction "24V_8") (pintype "passive"))
    )
    (net (code "108") (name "unconnected-(P3-GND-Pad29)") (class "Default")
      (node (ref "P3") (pin "29") (pinfunction "GND_29") (pintype "passive"))
    )
    (net (code "109") (name "unconnected-(P3-GND-Pad30)") (class "Default")
      (node (ref "P3") (pin "30") (pinfunction "GND_30") (pintype "passive"))
    )
    (net (code "110") (name "unconnected-(P3-GND-Pad31)") (class "Default")
      (node (ref "P3") (pin "31") (pinfunction "GND_31") (pintype "passive"))
    )
    (net (code "111") (name "unconnected-(P3-GND-Pad32)") (class "Default")
      (node (ref "P3") (pin "32") (pinfunction "GND_32") (pintype "passive"))
    )
    (net (code "112") (name "unconnected-(P3-GND-Pad33)") (class "Default")
      (node (ref "P3") (pin "33") (pinfunction "GND_33") (pintype "passive"))
    )
    (net (code "113") (name "unconnected-(P3-GND-Pad34)") (class "Default")
      (node (ref "P3") (pin "34") (pinfunction "GND_34") (pintype "passive"))
    )
    (net (code "114") (name "unconnected-(P3-GND-Pad35)") (class "Default")
      (node (ref "P3") (pin "35") (pinfunction "GND_35") (pintype "passive"))
    )
    (net (code "115") (name "unconnected-(P3-GND-Pad36)") (class "Default")
      (node (ref "P3") (pin "36") (pinfunction "GND_36") (pintype "passive"))
    )
    (net (code "116") (name "unconnected-(SIP3-Pad4)") (class "Default")
      (node (ref "SIP3") (pin "4") (pinfunction "4_4") (pintype "passive"))
    )
    (net (code "117") (name "unconnected-(U1-3.3V-Pad40)") (class "Default")
      (node (ref "U1") (pin "40") (pinfunction "3.3V_40") (pintype "passive"))
    )
    (net (code "118") (name "unconnected-(U1-5V-Pad2)") (class "Default")
      (node (ref "U1") (pin "2") (pinfunction "5V_2") (pintype "passive"))
    )
    (net (code "119") (name "unconnected-(U1-5V-Pad25)") (class "Default")
      (node (ref "U1") (pin "25") (pinfunction "5V_25") (pintype "passive"))
    )
    (net (code "120") (name "unconnected-(U1-5V-Pad29)") (class "Default")
      (node (ref "U1") (pin "29") (pinfunction "5V_29") (pintype "passive"))
    )
    (net (code "121") (name "unconnected-(U1-GND-Pad1)") (class "Default")
      (node (ref "U1") (pin "1") (pinfunction "GND_1") (pintype "passive"))
    )
    (net (code "122") (name "unconnected-(U1-GND-Pad26)") (class "Default")
      (node (ref "U1") (pin "26") (pinfunction "GND_26") (pintype "passive"))
    )
    (net (code "123") (name "unconnected-(U1-GND-Pad30)") (class "Default")
      (node (ref "U1") (pin "30") (pinfunction "GND_30") (pintype "passive"))
    )
    (net (code "124") (name "unconnected-(U1-MOSI-Pad41)") (class "Default")
      (node (ref "U1") (pin "41") (pinfunction "MOSI_41") (pintype "passive"))
    )
    (net (code "125") (name "unconnected-(U1-MOSO-Pad42)") (class "Default")
      (node (ref "U1") (pin "42") (pinfunction "MOSO_42") (pintype "passive"))
    )
    (net (code "126") (name "unconnected-(U1-NSS-Pad44)") (class "Default")
      (node (ref "U1") (pin "44") (pinfunction "NSS_44") (pintype "passive"))
    )
    (net (code "127") (name "unconnected-(U1-PC0-Pad51)") (class "Default")
      (node (ref "U1") (pin "51") (pinfunction "PC0_51") (pintype "passive"))
    )
    (net (code "128") (name "unconnected-(U1-PC1-Pad52)") (class "Default")
      (node (ref "U1") (pin "52") (pinfunction "PC1_52") (pintype "passive"))
    )
    (net (code "129") (name "unconnected-(U1-RX3-Pad32)") (class "Default")
      (node (ref "U1") (pin "32") (pinfunction "RX3_32") (pintype "passive"))
    )
    (net (code "130") (name "unconnected-(U1-RX6-Pad28)") (class "Default")
      (node (ref "U1") (pin "28") (pinfunction "RX6_28") (pintype "passive"))
    )
    (net (code "131") (name "unconnected-(U1-SCK-Pad43)") (class "Default")
      (node (ref "U1") (pin "43") (pinfunction "SCK_43") (pintype "passive"))
    )
    (net (code "132") (name "unconnected-(U1-T2_-Pad12)") (class "Default")
      (node (ref "U1") (pin "12") (pinfunction "T2__12") (pintype "passive"))
    )
    (net (code "133") (name "unconnected-(U1-T2_2-Pad9)") (class "Default")
      (node (ref "U1") (pin "9") (pinfunction "T2_2_9") (pintype "passive"))
    )
    (net (code "134") (name "unconnected-(U1-T9_1-Pad4)") (class "Default")
      (node (ref "U1") (pin "4") (pinfunction "T9_1_4") (pintype "passive"))
    )
    (net (code "135") (name "unconnected-(U1-T9_2-Pad3)") (class "Default")
      (node (ref "U1") (pin "3") (pinfunction "T9_2_3") (pintype "passive"))
    )
    (net (code "136") (name "unconnected-(U1-TX3-Pad31)") (class "Default")
      (node (ref "U1") (pin "31") (pinfunction "TX3_31") (pintype "passive"))
    )
    (net (code "137") (name "unconnected-(U1-TX6-Pad27)") (class "Default")
      (node (ref "U1") (pin "27") (pinfunction "TX6_27") (pintype "passive"))
    )
    (net (code "138") (name "unconnected-(U2-2-Pad67)") (class "Default")
      (node (ref "U2") (pin "67") (pinfunction "2_67") (pintype "passive"))
    )
    (net (code "139") (name "unconnected-(U2-3.3V-Pad2)") (class "Default")
      (node (ref "U2") (pin "2") (pinfunction "3.3V_2") (pintype "passive"))
    )
    (net (code "140") (name "unconnected-(U2-5V-Pad81)") (class "Default")
      (node (ref "U2") (pin "81") (pinfunction "5V_81") (pintype "passive"))
    )
    (net (code "141") (name "unconnected-(U2-5V-Pad82)") (class "Default")
      (node (ref "U2") (pin "82") (pinfunction "5V_82") (pintype "passive"))
    )
    (net (code "142") (name "unconnected-(U2-13-Pad78)") (class "Default")
      (node (ref "U2") (pin "78") (pinfunction "13_78") (pintype "passive"))
    )
    (net (code "143") (name "unconnected-(U2-22-Pad23)") (class "Default")
      (node (ref "U2") (pin "23") (pinfunction "22_23") (pintype "passive"))
    )
    (net (code "144") (name "unconnected-(U2-24-Pad25)") (class "Default")
      (node (ref "U2") (pin "25") (pinfunction "24_25") (pintype "passive"))
    )
    (net (code "145") (name "unconnected-(U2-26-Pad27)") (class "Default")
      (node (ref "U2") (pin "27") (pinfunction "26_27") (pintype "passive"))
    )
    (net (code "146") (name "unconnected-(U2-28-Pad29)") (class "Default")
      (node (ref "U2") (pin "29") (pinfunction "28_29") (pintype "passive"))
    )
    (net (code "147") (name "unconnected-(U2-30-Pad31)") (class "Default")
      (node (ref "U2") (pin "31") (pinfunction "30_31") (pintype "passive"))
    )
    (net (code "148") (name "unconnected-(U2-31-Pad32)") (class "Default")
      (node (ref "U2") (pin "32") (pinfunction "31_32") (pintype "passive"))
    )
    (net (code "149") (name "unconnected-(U2-32-Pad33)") (class "Default")
      (node (ref "U2") (pin "33") (pinfunction "32_33") (pintype "passive"))
    )
    (net (code "150") (name "unconnected-(U2-33-Pad34)") (class "Default")
      (node (ref "U2") (pin "34") (pinfunction "33_34") (pintype "passive"))
    )
    (net (code "151") (name "unconnected-(U2-34-Pad35)") (class "Default")
      (node (ref "U2") (pin "35") (pinfunction "34_35") (pintype "passive"))
    )
    (net (code "152") (name "unconnected-(U2-35-Pad36)") (class "Default")
      (node (ref "U2") (pin "36") (pinfunction "35_36") (pintype "passive"))
    )
    (net (code "153") (name "unconnected-(U2-36-Pad37)") (class "Default")
      (node (ref "U2") (pin "37") (pinfunction "36_37") (pintype "passive"))
    )
    (net (code "154") (name "unconnected-(U2-37-Pad38)") (class "Default")
      (node (ref "U2") (pin "38") (pinfunction "37_38") (pintype "passive"))
    )
    (net (code "155") (name "unconnected-(U2-38-Pad39)") (class "Default")
      (node (ref "U2") (pin "39") (pinfunction "38_39") (pintype "passive"))
    )
    (net (code "156") (name "unconnected-(U2-39-Pad40)") (class "Default")
      (node (ref "U2") (pin "40") (pinfunction "39_40") (pintype "passive"))
    )
    (net (code "157") (name "unconnected-(U2-40-Pad41)") (class "Default")
      (node (ref "U2") (pin "41") (pinfunction "40_41") (pintype "passive"))
    )
    (net (code "158") (name "unconnected-(U2-41-Pad42)") (class "Default")
      (node (ref "U2") (pin "42") (pinfunction "41_42") (pintype "passive"))
    )
    (net (code "159") (name "unconnected-(U2-42-Pad43)") (class "Default")
      (node (ref "U2") (pin "43") (pinfunction "42_43") (pintype "passive"))
    )
    (net (code "160") (name "unconnected-(U2-43-Pad44)") (class "Default")
      (node (ref "U2") (pin "44") (pinfunction "43_44") (pintype "passive"))
    )
    (net (code "161") (name "unconnected-(U2-44-Pad45)") (class "Default")
      (node (ref "U2") (pin "45") (pinfunction "44_45") (pintype "passive"))
    )
    (net (code "162") (name "unconnected-(U2-45-Pad46)") (class "Default")
      (node (ref "U2") (pin "46") (pinfunction "45_46") (pintype "passive"))
    )
    (net (code "163") (name "unconnected-(U2-46-Pad47)") (class "Default")
      (node (ref "U2") (pin "47") (pinfunction "46_47") (pintype "passive"))
    )
    (net (code "164") (name "unconnected-(U2-47-Pad48)") (class "Default")
      (node (ref "U2") (pin "48") (pinfunction "47_48") (pintype "passive"))
    )
    (net (code "165") (name "unconnected-(U2-48-Pad49)") (class "Default")
      (node (ref "U2") (pin "49") (pinfunction "48_49") (pintype "passive"))
    )
    (net (code "166") (name "unconnected-(U2-49-Pad50)") (class "Default")
      (node (ref "U2") (pin "50") (pinfunction "49_50") (pintype "passive"))
    )
    (net (code "167") (name "unconnected-(U2-50-Pad51)") (class "Default")
      (node (ref "U2") (pin "51") (pinfunction "50_51") (pintype "passive"))
    )
    (net (code "168") (name "unconnected-(U2-51-Pad52)") (class "Default")
      (node (ref "U2") (pin "52") (pinfunction "51_52") (pintype "passive"))
    )
    (net (code "169") (name "unconnected-(U2-52-Pad53)") (class "Default")
      (node (ref "U2") (pin "53") (pinfunction "52_53") (pintype "passive"))
    )
    (net (code "170") (name "unconnected-(U2-53-Pad54)") (class "Default")
      (node (ref "U2") (pin "54") (pinfunction "53_54") (pintype "passive"))
    )
    (net (code "171") (name "unconnected-(U2-54-Pad55)") (class "Default")
      (node (ref "U2") (pin "55") (pinfunction "54_55") (pintype "passive"))
    )
    (net (code "172") (name "unconnected-(U2-A1-Pad8)") (class "Default")
      (node (ref "U2") (pin "8") (pinfunction "A1_8") (pintype "passive"))
    )
    (net (code "173") (name "unconnected-(U2-A2-Pad9)") (class "Default")
      (node (ref "U2") (pin "9") (pinfunction "A2_9") (pintype "passive"))
    )
    (net (code "174") (name "unconnected-(U2-A3-Pad10)") (class "Default")
      (node (ref "U2") (pin "10") (pinfunction "A3_10") (pintype "passive"))
    )
    (net (code "175") (name "unconnected-(U2-A4-Pad11)") (class "Default")
      (node (ref "U2") (pin "11") (pinfunction "A4_11") (pintype "passive"))
    )
    (net (code "176") (name "unconnected-(U2-A5-Pad12)") (class "Default")
      (node (ref "U2") (pin "12") (pinfunction "A5_12") (pintype "passive"))
    )
    (net (code "177") (name "unconnected-(U2-A6-Pad13)") (class "Default")
      (node (ref "U2") (pin "13") (pinfunction "A6_13") (pintype "passive"))
    )
    (net (code "178") (name "unconnected-(U2-A7-Pad14)") (class "Default")
      (node (ref "U2") (pin "14") (pinfunction "A7_14") (pintype "passive"))
    )
    (net (code "179") (name "unconnected-(U2-A8-Pad15)") (class "Default")
      (node (ref "U2") (pin "15") (pinfunction "A8_15") (pintype "passive"))
    )
    (net (code "180") (name "unconnected-(U2-A9-Pad16)") (class "Default")
      (node (ref "U2") (pin "16") (pinfunction "A9_16") (pintype "passive"))
    )
    (net (code "181") (name "unconnected-(U2-A10-Pad17)") (class "Default")
      (node (ref "U2") (pin "17") (pinfunction "A10_17") (pintype "passive"))
    )
    (net (code "182") (name "unconnected-(U2-A11-Pad18)") (class "Default")
      (node (ref "U2") (pin "18") (pinfunction "A11_18") (pintype "passive"))
    )
    (net (code "183") (name "unconnected-(U2-A12-Pad19)") (class "Default")
      (node (ref "U2") (pin "19") (pinfunction "A12_19") (pintype "passive"))
    )
    (net (code "184") (name "unconnected-(U2-A13-Pad20)") (class "Default")
      (node (ref "U2") (pin "20") (pinfunction "A13_20") (pintype "passive"))
    )
    (net (code "185") (name "unconnected-(U2-A14-Pad21)") (class "Default")
      (node (ref "U2") (pin "21") (pinfunction "A14_21") (pintype "passive"))
    )
    (net (code "186") (name "unconnected-(U2-A15-Pad22)") (class "Default")
      (node (ref "U2") (pin "22") (pinfunction "A15_22") (pintype "passive"))
    )
    (net (code "187") (name "unconnected-(U2-AREF-Pad80)") (class "Default")
      (node (ref "U2") (pin "80") (pinfunction "AREF_80") (pintype "passive"))
    )
    (net (code "188") (name "unconnected-(U2-GND-Pad56)") (class "Default")
      (node (ref "U2") (pin "56") (pinfunction "GND_56") (pintype "passive"))
    )
    (net (code "189") (name "unconnected-(U2-GND-Pad79)") (class "Default")
      (node (ref "U2") (pin "79") (pinfunction "GND_79") (pintype "passive"))
    )
    (net (code "190") (name "unconnected-(U2-RESET-Pad1)") (class "Default")
      (node (ref "U2") (pin "1") (pinfunction "RESET_1") (pintype "passive"))
    )
    (net (code "191") (name "unconnected-(U2-RX0-Pad65)") (class "Default")
      (node (ref "U2") (pin "65") (pinfunction "RX0_65") (pintype "passive"))
    )
    (net (code "192") (name "unconnected-(U2-RX1-Pad59)") (class "Default")
      (node (ref "U2") (pin "59") (pinfunction "RX1_59") (pintype "passive"))
    )
    (net (code "193") (name "unconnected-(U2-RX3-Pad63)") (class "Default")
      (node (ref "U2") (pin "63") (pinfunction "RX3_63") (pintype "passive"))
    )
    (net (code "194") (name "unconnected-(U2-SCL-Pad57)") (class "Default")
      (node (ref "U2") (pin "57") (pinfunction "SCL_57") (pintype "passive"))
    )
    (net (code "195") (name "unconnected-(U2-SDA-Pad58)") (class "Default")
      (node (ref "U2") (pin "58") (pinfunction "SDA_58") (pintype "passive"))
    )
    (net (code "196") (name "unconnected-(U2-TX0-Pad66)") (class "Default")
      (node (ref "U2") (pin "66") (pinfunction "TX0_66") (pintype "passive"))
    )
    (net (code "197") (name "unconnected-(U2-TX1-Pad60)") (class "Default")
      (node (ref "U2") (pin "60") (pinfunction "TX1_60") (pintype "passive"))
    )
    (net (code "198") (name "unconnected-(U2-TX3-Pad64)") (class "Default")
      (node (ref "U2") (pin "64") (pinfunction "TX3_64") (pintype "passive"))
    )
    (net (code "199") (name "unconnected-(U2-Vin-Pad6)") (class "Default")
      (node (ref "U2") (pin "6") (pinfunction "Vin_6") (pintype "passive"))
    )
  )
)
